# TestBoardRevB.net
KiCad netlist of a schematic drawn in EAGLE
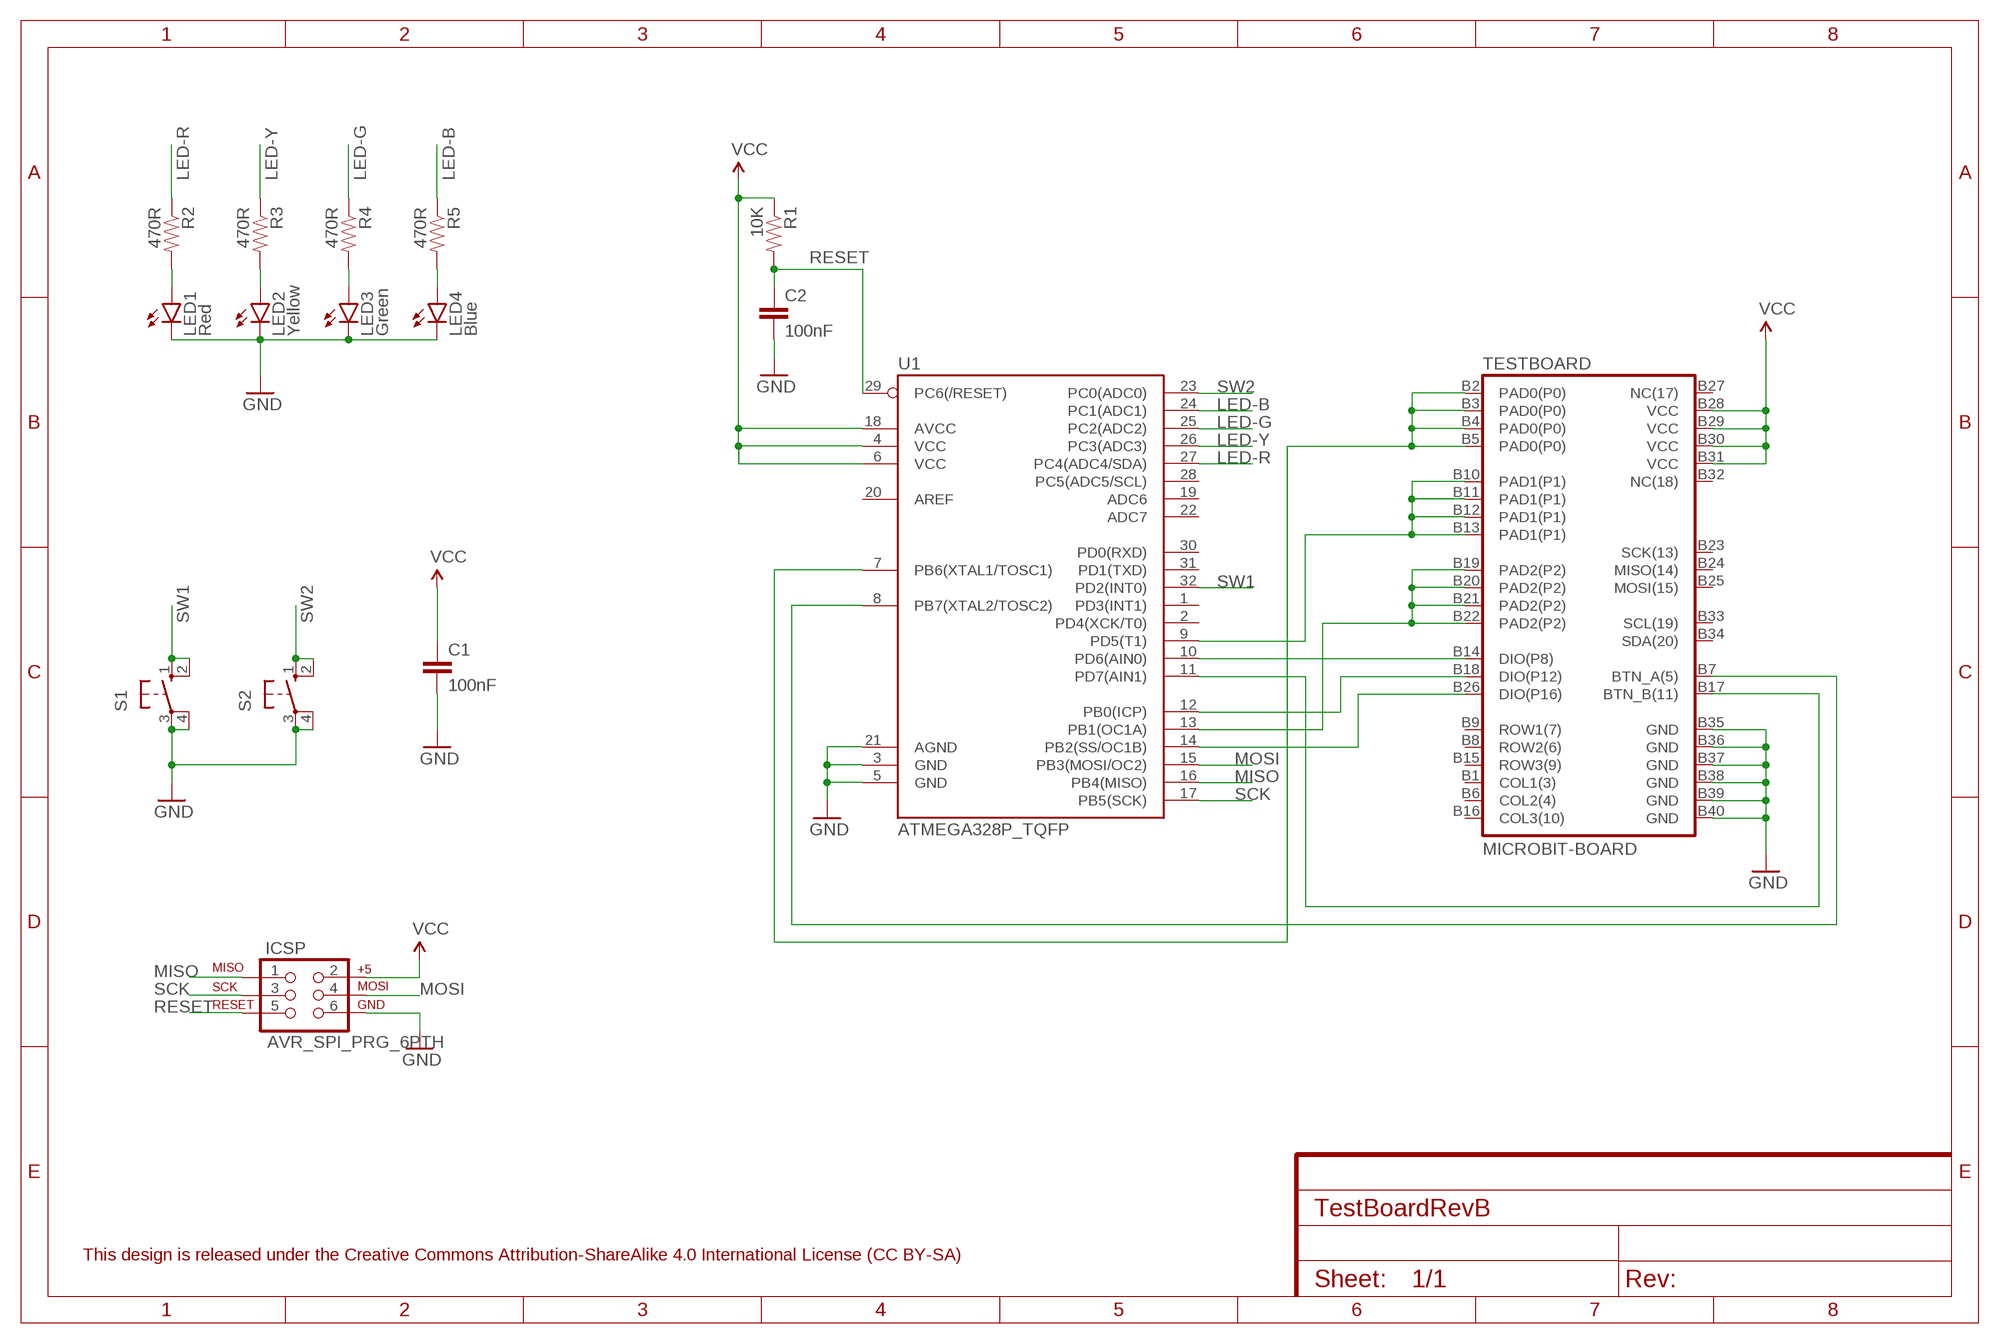
[diagram p0: schematic, sheet 1]

(export (version "E")
  (design (tool "Eeschema 10.0.6"))
  (components
    (comp (ref "C1")
      (value "100nF")
      (footprint "eagle-import:0603-CAP")
      (libsource (lib "eagle-import") (part "CAP0603-CAP"))
    )
    (comp (ref "C2")
      (value "100nF")
      (footprint "eagle-import:0603-CAP")
      (libsource (lib "eagle-import") (part "CAP0603-CAP"))
    )
    (comp (ref "ICSP")
      (value "AVR_SPI_PRG_6PTH")
      (footprint "eagle-import:2X3")
      (libsource (lib "eagle-import") (part "AVR_SPI_PRG_6PTH"))
    )
    (comp (ref "LED1")
      (value "Red")
      (footprint "eagle-import:LED-0603")
      (libsource (lib "eagle-import") (part "LED0603"))
    )
    (comp (ref "LED2")
      (value "Yellow")
      (footprint "eagle-import:LED-0603")
      (libsource (lib "eagle-import") (part "LED0603"))
    )
    (comp (ref "LED3")
      (value "Green")
      (footprint "eagle-import:LED-0603")
      (libsource (lib "eagle-import") (part "LED0603"))
    )
    (comp (ref "LED4")
      (value "Blue")
      (footprint "eagle-import:LED-0603")
      (libsource (lib "eagle-import") (part "LED0603"))
    )
    (comp (ref "R1")
      (value "10K")
      (footprint "eagle-import:0603-RES")
      (libsource (lib "eagle-import") (part "RESISTOR0603-RES"))
    )
    (comp (ref "R2")
      (value "470R")
      (footprint "eagle-import:0603-RES")
      (libsource (lib "eagle-import") (part "RESISTOR0603-RES"))
    )
    (comp (ref "R3")
      (value "470R")
      (footprint "eagle-import:0603-RES")
      (libsource (lib "eagle-import") (part "RESISTOR0603-RES"))
    )
    (comp (ref "R4")
      (value "470R")
      (footprint "eagle-import:0603-RES")
      (libsource (lib "eagle-import") (part "RESISTOR0603-RES"))
    )
    (comp (ref "R5")
      (value "470R")
      (footprint "eagle-import:0603-RES")
      (libsource (lib "eagle-import") (part "RESISTOR0603-RES"))
    )
    (comp (ref "S1")
      (value "10-XX")
      (footprint "eagle-import:B3F-10XX")
      (fields (field (name "MPN") "B3F-1000"))
      (libsource (lib "eagle-import") (part "10-XX"))
    )
    (comp (ref "S2")
      (value "10-XX")
      (footprint "eagle-import:B3F-10XX")
      (fields (field (name "MPN") "B3F-1000"))
      (libsource (lib "eagle-import") (part "10-XX"))
    )
    (comp (ref "TESTBOARD")
      (value "MICROBIT-BOARD")
      (footprint "eagle-import:MICROBIT-EDGE-CONN")
      (libsource (lib "eagle-import") (part "MICROBIT-BOARD"))
    )
    (comp (ref "U1")
      (value "ATMEGA328P_TQFP")
      (footprint "eagle-import:TQFP32-08")
      (libsource (lib "eagle-import") (part "ATMEGA328P_TQFP"))
    )
  )
  (nets
    (net (code "1") (name "/LED-B") (class "Default")
      (node (ref "R5") (pin "1") (pinfunction "1_1") (pintype "passive"))
      (node (ref "U1") (pin "24") (pinfunction "PC1(ADC1)_24") (pintype "bidirectional"))
    )
    (net (code "2") (name "/LED-G") (class "Default")
      (node (ref "R4") (pin "1") (pinfunction "1_1") (pintype "passive"))
      (node (ref "U1") (pin "25") (pinfunction "PC2(ADC2)_25") (pintype "bidirectional"))
    )
    (net (code "3") (name "/LED-R") (class "Default")
      (node (ref "R2") (pin "1") (pinfunction "1_1") (pintype "passive"))
      (node (ref "U1") (pin "27") (pinfunction "PC4(ADC4/SDA)_27") (pintype "bidirectional"))
    )
    (net (code "4") (name "/LED-Y") (class "Default")
      (node (ref "R3") (pin "1") (pinfunction "1_1") (pintype "passive"))
      (node (ref "U1") (pin "26") (pinfunction "PC3(ADC3)_26") (pintype "bidirectional"))
    )
    (net (code "5") (name "/MISO") (class "Default")
      (node (ref "ICSP") (pin "1") (pinfunction "1_1") (pintype "passive"))
      (node (ref "U1") (pin "16") (pinfunction "PB4(MISO)_16") (pintype "bidirectional"))
    )
    (net (code "6") (name "/MOSI") (class "Default")
      (node (ref "ICSP") (pin "4") (pinfunction "4_4") (pintype "passive"))
      (node (ref "U1") (pin "15") (pinfunction "PB3(MOSI/OC2)_15") (pintype "bidirectional"))
    )
    (net (code "7") (name "/RESET") (class "Default")
      (node (ref "C2") (pin "1") (pinfunction "1_1") (pintype "passive"))
      (node (ref "ICSP") (pin "5") (pinfunction "5_5") (pintype "passive"))
      (node (ref "R1") (pin "2") (pinfunction "2_2") (pintype "passive"))
      (node (ref "U1") (pin "29") (pinfunction "PC6(/RESET)_29") (pintype "bidirectional"))
    )
    (net (code "8") (name "/SCK") (class "Default")
      (node (ref "ICSP") (pin "3") (pinfunction "3_3") (pintype "passive"))
      (node (ref "U1") (pin "17") (pinfunction "PB5(SCK)_17") (pintype "bidirectional"))
    )
    (net (code "9") (name "/SW1") (class "Default")
      (node (ref "S1") (pin "1") (pinfunction "S_1") (pintype "passive"))
      (node (ref "S1") (pin "2") (pinfunction "S1_2") (pintype "passive"))
      (node (ref "U1") (pin "32") (pinfunction "PD2(INT0)_32") (pintype "bidirectional"))
    )
    (net (code "10") (name "/SW2") (class "Default")
      (node (ref "S2") (pin "1") (pinfunction "S_1") (pintype "passive"))
      (node (ref "S2") (pin "2") (pinfunction "S1_2") (pintype "passive"))
      (node (ref "U1") (pin "23") (pinfunction "PC0(ADC0)_23") (pintype "bidirectional"))
    )
    (net (code "11") (name "GND") (class "Default")
      (node (ref "C1") (pin "2") (pinfunction "2_2") (pintype "passive"))
      (node (ref "C2") (pin "2") (pinfunction "2_2") (pintype "passive"))
      (node (ref "ICSP") (pin "6") (pinfunction "6_6") (pintype "passive"))
      (node (ref "LED1") (pin "C") (pinfunction "C_C") (pintype "passive"))
      (node (ref "LED2") (pin "C") (pinfunction "C_C") (pintype "passive"))
      (node (ref "LED3") (pin "C") (pinfunction "C_C") (pintype "passive"))
      (node (ref "LED4") (pin "C") (pinfunction "C_C") (pintype "passive"))
      (node (ref "S1") (pin "3") (pinfunction "P_3") (pintype "passive"))
      (node (ref "S1") (pin "4") (pinfunction "P1_4") (pintype "passive"))
      (node (ref "S2") (pin "3") (pinfunction "P_3") (pintype "passive"))
      (node (ref "S2") (pin "4") (pinfunction "P1_4") (pintype "passive"))
      (node (ref "TESTBOARD") (pin "B35") (pinfunction "GND_B35") (pintype "power_in"))
      (node (ref "TESTBOARD") (pin "B36") (pinfunction "GND_B36") (pintype "power_in"))
      (node (ref "TESTBOARD") (pin "B37") (pinfunction "GND_B37") (pintype "power_in"))
      (node (ref "TESTBOARD") (pin "B38") (pinfunction "GND_B38") (pintype "power_in"))
      (node (ref "TESTBOARD") (pin "B39") (pinfunction "GND_B39") (pintype "power_in"))
      (node (ref "TESTBOARD") (pin "B40") (pinfunction "GND_B40") (pintype "power_in"))
      (node (ref "U1") (pin "21") (pinfunction "AGND_21") (pintype "bidirectional"))
      (node (ref "U1") (pin "3") (pinfunction "GND_3") (pintype "bidirectional"))
      (node (ref "U1") (pin "5") (pinfunction "GND_5") (pintype "bidirectional"))
    )
    (net (code "12") (name "Net-(LED1-PadA)") (class "Default")
      (node (ref "LED1") (pin "A") (pinfunction "A_A") (pintype "passive"))
      (node (ref "R2") (pin "2") (pinfunction "2_2") (pintype "passive"))
    )
    (net (code "13") (name "Net-(LED2-PadA)") (class "Default")
      (node (ref "LED2") (pin "A") (pinfunction "A_A") (pintype "passive"))
      (node (ref "R3") (pin "2") (pinfunction "2_2") (pintype "passive"))
    )
    (net (code "14") (name "Net-(LED3-PadA)") (class "Default")
      (node (ref "LED3") (pin "A") (pinfunction "A_A") (pintype "passive"))
      (node (ref "R4") (pin "2") (pinfunction "2_2") (pintype "passive"))
    )
    (net (code "15") (name "Net-(LED4-PadA)") (class "Default")
      (node (ref "LED4") (pin "A") (pinfunction "A_A") (pintype "passive"))
      (node (ref "R5") (pin "2") (pinfunction "2_2") (pintype "passive"))
    )
    (net (code "16") (name "Net-(TESTBOARD-BTN_A(5))") (class "Default")
      (node (ref "TESTBOARD") (pin "B7") (pinfunction "BTN_A(5)_B7") (pintype "input"))
      (node (ref "U1") (pin "8") (pinfunction "PB7(XTAL2/TOSC2)_8") (pintype "bidirectional"))
    )
    (net (code "17") (name "Net-(TESTBOARD-BTN_B(11))") (class "Default")
      (node (ref "TESTBOARD") (pin "B17") (pinfunction "BTN_B(11)_B17") (pintype "input"))
      (node (ref "U1") (pin "11") (pinfunction "PD7(AIN1)_11") (pintype "bidirectional"))
    )
    (net (code "18") (name "Net-(TESTBOARD-DIO(P8))") (class "Default")
      (node (ref "TESTBOARD") (pin "B14") (pinfunction "DIO(P8)_B14") (pintype "bidirectional"))
      (node (ref "U1") (pin "10") (pinfunction "PD6(AIN0)_10") (pintype "bidirectional"))
    )
    (net (code "19") (name "Net-(TESTBOARD-DIO(P12))") (class "Default")
      (node (ref "TESTBOARD") (pin "B18") (pinfunction "DIO(P12)_B18") (pintype "bidirectional"))
      (node (ref "U1") (pin "12") (pinfunction "PB0(ICP)_12") (pintype "bidirectional"))
    )
    (net (code "20") (name "Net-(TESTBOARD-DIO(P16))") (class "Default")
      (node (ref "TESTBOARD") (pin "B26") (pinfunction "DIO(P16)_B26") (pintype "bidirectional"))
      (node (ref "U1") (pin "14") (pinfunction "PB2(SS/OC1B)_14") (pintype "bidirectional"))
    )
    (net (code "21") (name "Net-(U1-PB1(OC1A))") (class "Default")
      (node (ref "TESTBOARD") (pin "B19") (pinfunction "PAD2(P2)_B19") (pintype "bidirectional"))
      (node (ref "TESTBOARD") (pin "B20") (pinfunction "PAD2(P2)_B20") (pintype "bidirectional"))
      (node (ref "TESTBOARD") (pin "B21") (pinfunction "PAD2(P2)_B21") (pintype "bidirectional"))
      (node (ref "TESTBOARD") (pin "B22") (pinfunction "PAD2(P2)_B22") (pintype "bidirectional"))
      (node (ref "U1") (pin "13") (pinfunction "PB1(OC1A)_13") (pintype "bidirectional"))
    )
    (net (code "22") (name "Net-(U1-PB6(XTAL1{slash}TOSC1))") (class "Default")
      (node (ref "TESTBOARD") (pin "B2") (pinfunction "PAD0(P0)_B2") (pintype "bidirectional"))
      (node (ref "TESTBOARD") (pin "B3") (pinfunction "PAD0(P0)_B3") (pintype "bidirectional"))
      (node (ref "TESTBOARD") (pin "B4") (pinfunction "PAD0(P0)_B4") (pintype "bidirectional"))
      (node (ref "TESTBOARD") (pin "B5") (pinfunction "PAD0(P0)_B5") (pintype "bidirectional"))
      (node (ref "U1") (pin "7") (pinfunction "PB6(XTAL1/TOSC1)_7") (pintype "bidirectional"))
    )
    (net (code "23") (name "Net-(U1-PD5(T1))") (class "Default")
      (node (ref "TESTBOARD") (pin "B10") (pinfunction "PAD1(P1)_B10") (pintype "bidirectional"))
      (node (ref "TESTBOARD") (pin "B11") (pinfunction "PAD1(P1)_B11") (pintype "bidirectional"))
      (node (ref "TESTBOARD") (pin "B12") (pinfunction "PAD1(P1)_B12") (pintype "bidirectional"))
      (node (ref "TESTBOARD") (pin "B13") (pinfunction "PAD1(P1)_B13") (pintype "bidirectional"))
      (node (ref "U1") (pin "9") (pinfunction "PD5(T1)_9") (pintype "bidirectional"))
    )
    (net (code "24") (name "VCC") (class "Default")
      (node (ref "C1") (pin "1") (pinfunction "1_1") (pintype "passive"))
      (node (ref "ICSP") (pin "2") (pinfunction "2_2") (pintype "passive"))
      (node (ref "R1") (pin "1") (pinfunction "1_1") (pintype "passive"))
      (node (ref "TESTBOARD") (pin "B28") (pinfunction "VCC_B28") (pintype "power_in"))
      (node (ref "TESTBOARD") (pin "B29") (pinfunction "VCC_B29") (pintype "power_in"))
      (node (ref "TESTBOARD") (pin "B30") (pinfunction "VCC_B30") (pintype "power_in"))
      (node (ref "TESTBOARD") (pin "B31") (pinfunction "VCC_B31") (pintype "power_in"))
      (node (ref "U1") (pin "18") (pinfunction "AVCC_18") (pintype "bidirectional"))
      (node (ref "U1") (pin "4") (pinfunction "VCC_4") (pintype "bidirectional"))
      (node (ref "U1") (pin "6") (pinfunction "VCC_6") (pintype "bidirectional"))
    )
    (net (code "25") (name "unconnected-(TESTBOARD-COL1(3)-PadB1)") (class "Default")
      (node (ref "TESTBOARD") (pin "B1") (pinfunction "COL1(3)_B1") (pintype "output"))
    )
    (net (code "26") (name "unconnected-(TESTBOARD-COL2(4)-PadB6)") (class "Default")
      (node (ref "TESTBOARD") (pin "B6") (pinfunction "COL2(4)_B6") (pintype "output"))
    )
    (net (code "27") (name "unconnected-(TESTBOARD-COL3(10)-PadB16)") (class "Default")
      (node (ref "TESTBOARD") (pin "B16") (pinfunction "COL3(10)_B16") (pintype "output"))
    )
    (net (code "28") (name "unconnected-(TESTBOARD-MISO(14)-PadB24)") (class "Default")
      (node (ref "TESTBOARD") (pin "B24") (pinfunction "MISO(14)_B24") (pintype "bidirectional"))
    )
    (net (code "29") (name "unconnected-(TESTBOARD-MOSI(15)-PadB25)") (class "Default")
      (node (ref "TESTBOARD") (pin "B25") (pinfunction "MOSI(15)_B25") (pintype "bidirectional"))
    )
    (net (code "30") (name "unconnected-(TESTBOARD-NC(17)-PadB27)") (class "Default")
      (node (ref "TESTBOARD") (pin "B27") (pinfunction "NC(17)_B27") (pintype "no_connect"))
    )
    (net (code "31") (name "unconnected-(TESTBOARD-NC(18)-PadB32)") (class "Default")
      (node (ref "TESTBOARD") (pin "B32") (pinfunction "NC(18)_B32") (pintype "no_connect"))
    )
    (net (code "32") (name "unconnected-(TESTBOARD-ROW1(7)-PadB9)") (class "Default")
      (node (ref "TESTBOARD") (pin "B9") (pinfunction "ROW1(7)_B9") (pintype "output"))
    )
    (net (code "33") (name "unconnected-(TESTBOARD-ROW2(6)-PadB8)") (class "Default")
      (node (ref "TESTBOARD") (pin "B8") (pinfunction "ROW2(6)_B8") (pintype "output"))
    )
    (net (code "34") (name "unconnected-(TESTBOARD-ROW3(9)-PadB15)") (class "Default")
      (node (ref "TESTBOARD") (pin "B15") (pinfunction "ROW3(9)_B15") (pintype "output"))
    )
    (net (code "35") (name "unconnected-(TESTBOARD-SCK(13)-PadB23)") (class "Default")
      (node (ref "TESTBOARD") (pin "B23") (pinfunction "SCK(13)_B23") (pintype "bidirectional"))
    )
    (net (code "36") (name "unconnected-(TESTBOARD-SCL(19)-PadB33)") (class "Default")
      (node (ref "TESTBOARD") (pin "B33") (pinfunction "SCL(19)_B33") (pintype "bidirectional"))
    )
    (net (code "37") (name "unconnected-(TESTBOARD-SDA(20)-PadB34)") (class "Default")
      (node (ref "TESTBOARD") (pin "B34") (pinfunction "SDA(20)_B34") (pintype "bidirectional"))
    )
    (net (code "38") (name "unconnected-(U1-ADC6-Pad19)") (class "Default")
      (node (ref "U1") (pin "19") (pinfunction "ADC6_19") (pintype "bidirectional"))
    )
    (net (code "39") (name "unconnected-(U1-ADC7-Pad22)") (class "Default")
      (node (ref "U1") (pin "22") (pinfunction "ADC7_22") (pintype "bidirectional"))
    )
    (net (code "40") (name "unconnected-(U1-AREF-Pad20)") (class "Default")
      (node (ref "U1") (pin "20") (pinfunction "AREF_20") (pintype "bidirectional"))
    )
    (net (code "41") (name "unconnected-(U1-PC5(ADC5{slash}SCL)-Pad28)") (class "Default")
      (node (ref "U1") (pin "28") (pinfunction "PC5(ADC5/SCL)_28") (pintype "bidirectional"))
    )
    (net (code "42") (name "unconnected-(U1-PD0(RXD)-Pad30)") (class "Default")
      (node (ref "U1") (pin "30") (pinfunction "PD0(RXD)_30") (pintype "bidirectional"))
    )
    (net (code "43") (name "unconnected-(U1-PD1(TXD)-Pad31)") (class "Default")
      (node (ref "U1") (pin "31") (pinfunction "PD1(TXD)_31") (pintype "bidirectional"))
    )
    (net (code "44") (name "unconnected-(U1-PD3(INT1)-Pad1)") (class "Default")
      (node (ref "U1") (pin "1") (pinfunction "PD3(INT1)_1") (pintype "bidirectional"))
    )
    (net (code "45") (name "unconnected-(U1-PD4(XCK{slash}T0)-Pad2)") (class "Default")
      (node (ref "U1") (pin "2") (pinfunction "PD4(XCK/T0)_2") (pintype "bidirectional"))
    )
  )
)
